# easyEDA.net
KiCad netlist of a schematic drawn in EasyEDA
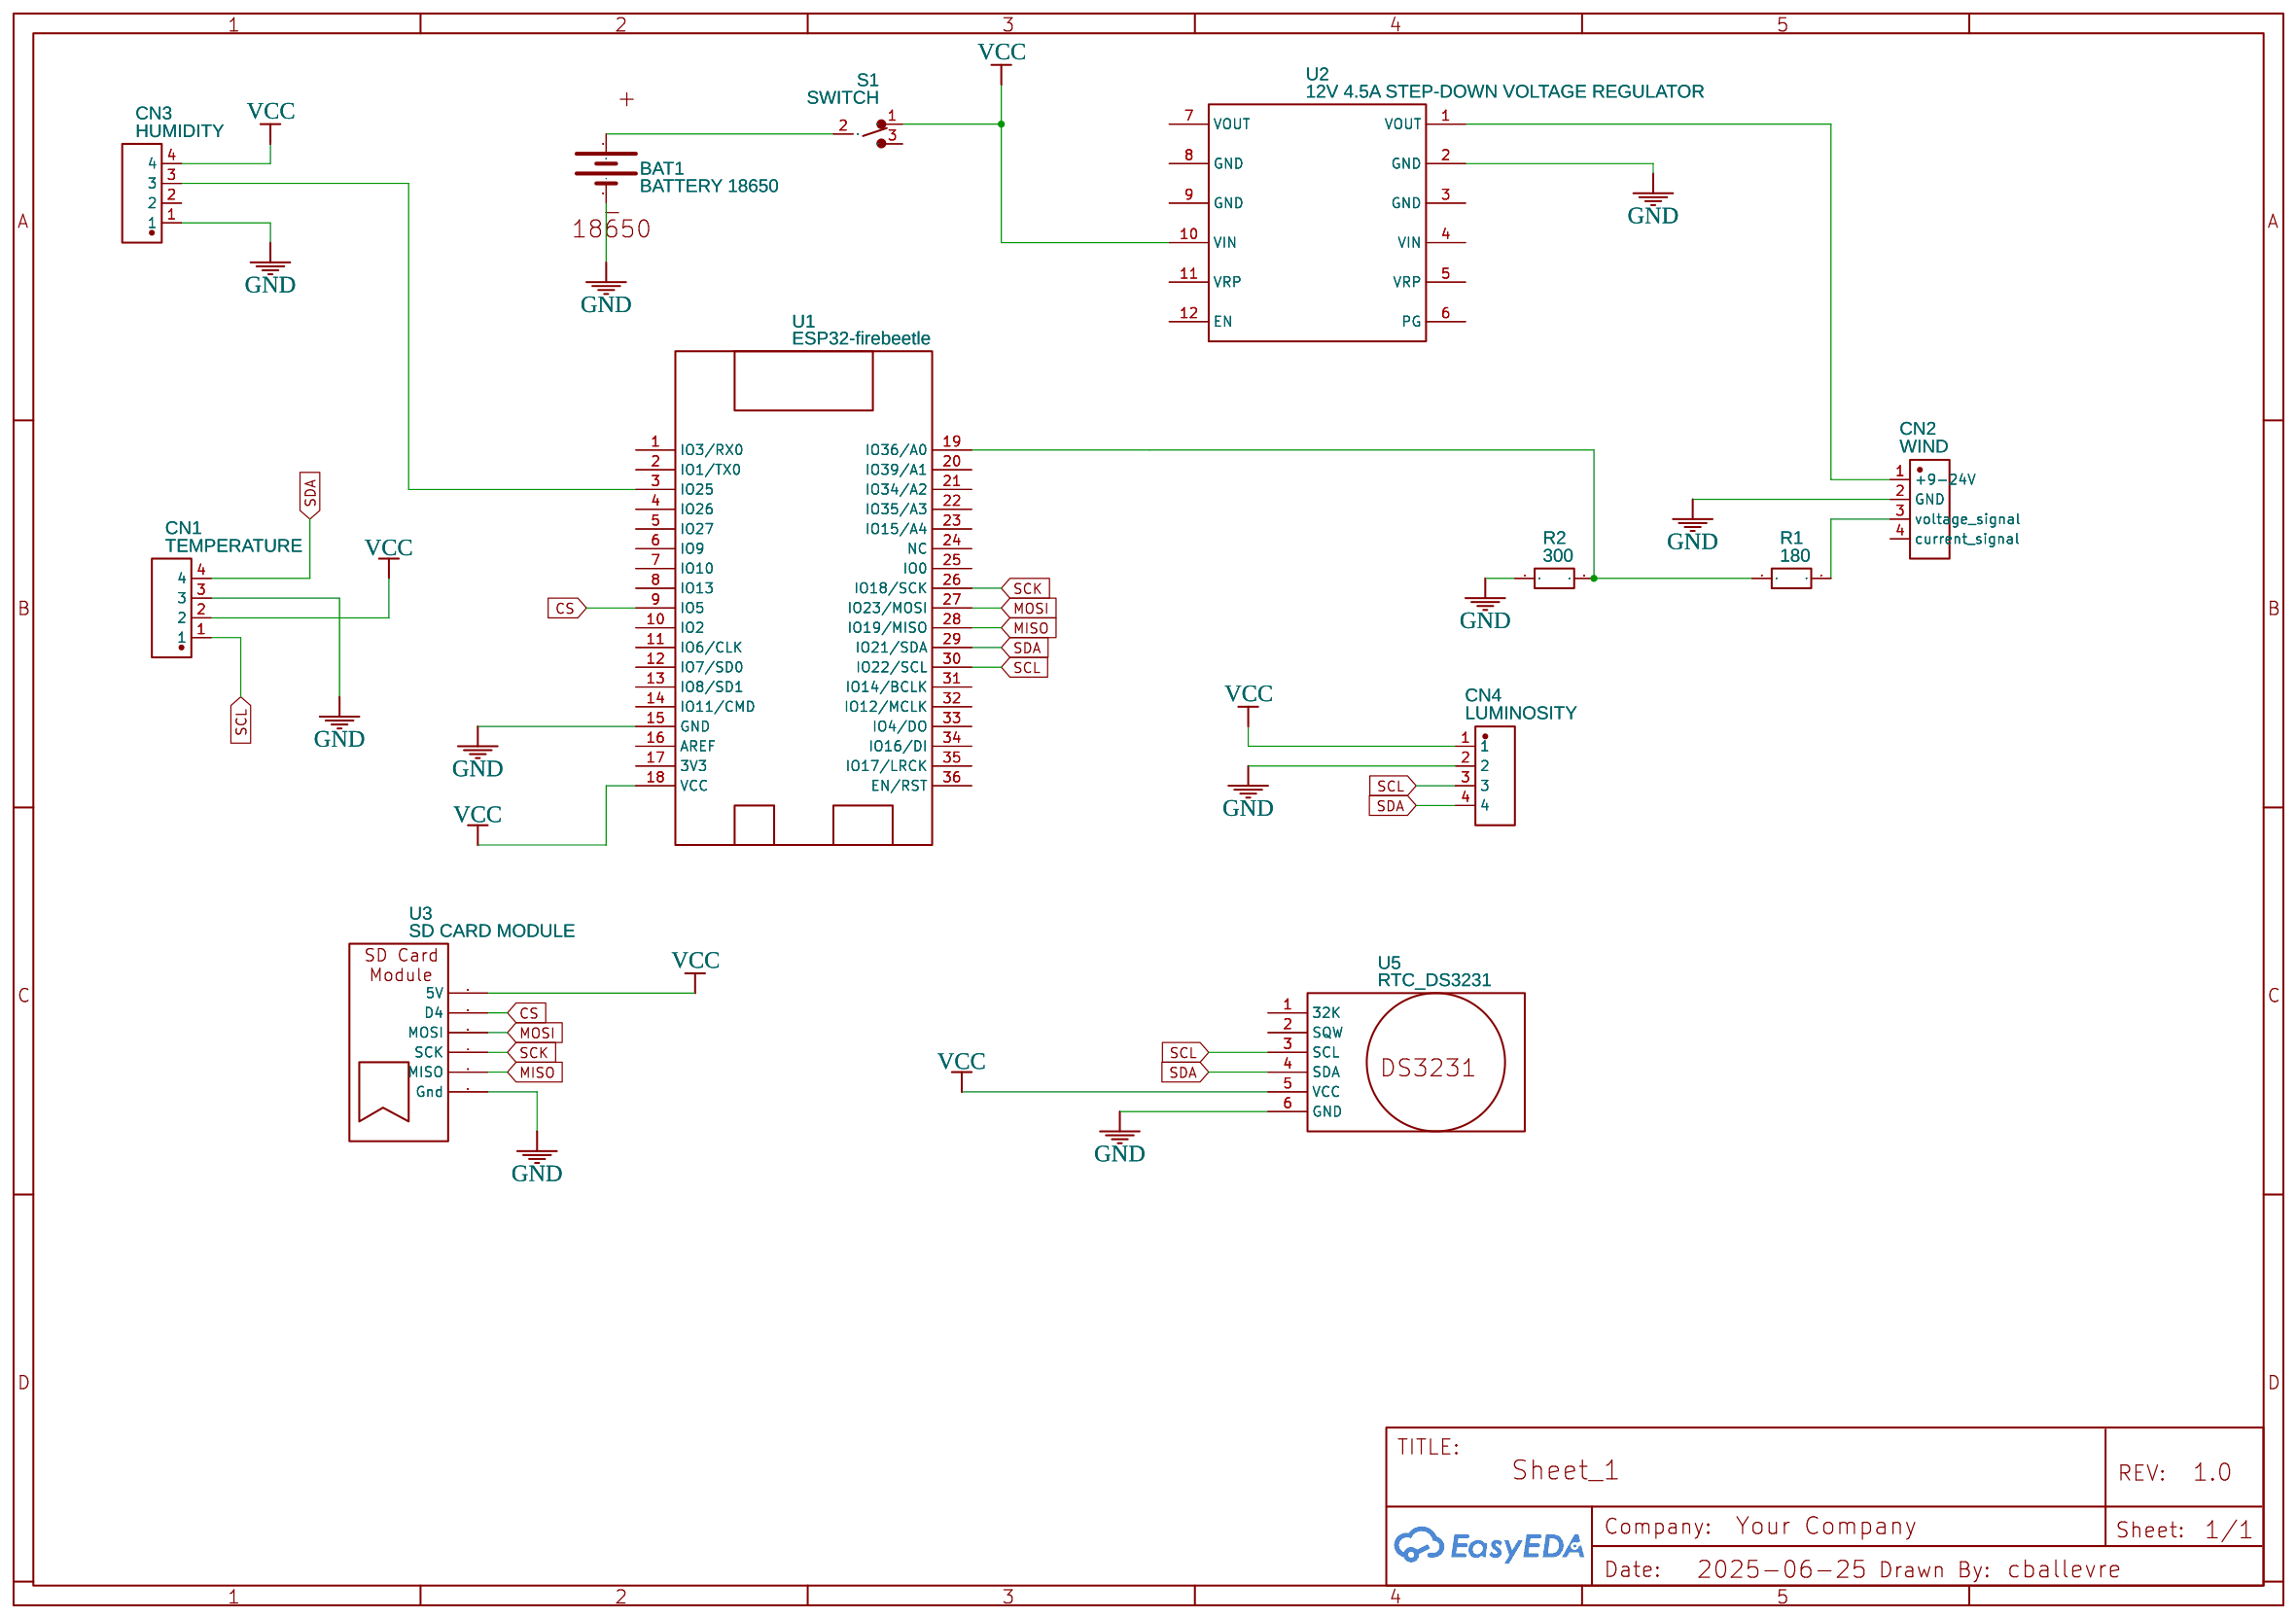
[diagram p0: schematic sheet]

(export (version "E")
  (design (tool "Eeschema 10.0.6"))
  (components
    (comp (ref "BAT1")
      (value "BATTERY 18650")
      (fields (field (name "Manufacturer Part") "battery"))
      (libsource (lib "") (part "BATTERY 18650"))
    )
    (comp (ref "CN1")
      (value "TEMPERATURE")
      (fields (field (name "Manufacturer Part") "Straight 4 pins magnetic connector Female"))
      (libsource (lib "") (part "STRAIGHT 4 PINS MAGNETIC CONNECTOR FEMALE"))
    )
    (comp (ref "CN2")
      (value "WIND")
      (fields (field (name "Manufacturer Part") "Straight 4 pins magnetic connector Female"))
      (libsource (lib "") (part "STRAIGHT 4 PINS MAGNETIC CONNECTOR FEMALE_1"))
    )
    (comp (ref "CN3")
      (value "HUMIDITY")
      (fields (field (name "Manufacturer Part") "Straight 4 pins magnetic connector Female"))
      (libsource (lib "") (part "STRAIGHT 4 PINS MAGNETIC CONNECTOR FEMALE"))
    )
    (comp (ref "CN4")
      (value "LUMINOSITY")
      (fields (field (name "Manufacturer Part") "Straight 4 pins magnetic connector Female"))
      (libsource (lib "") (part "STRAIGHT 4 PINS MAGNETIC CONNECTOR FEMALE_2"))
    )
    (comp (ref "R1") (value "180") (libsource (lib "") (part "R_0603_EU")))
    (comp (ref "R2") (value "300") (libsource (lib "") (part "R_0603_EU")))
    (comp (ref "S1") (value "SWITCH") (libsource (lib "") (part "SWITCH-SLIDE-SPDT-200MA-30V")))
    (comp (ref "U1") (value "ESP32-firebeetle") (libsource (lib "") (part "ESP32-firebeetle")))
    (comp (ref "U2")
      (value "12V 4.5A STEP-DOWN VOLTAGE REGULATOR")
      (libsource (lib "") (part "12V 4.5A STEP-DOWN VOLTAGE REGULATOR"))
    )
    (comp (ref "U3")
      (value "SD CARD MODULE")
      (fields (field (name "Manufacturer Part") "sd card module"))
      (libsource (lib "") (part "SD CARD MODULE COPY JEF"))
    )
    (comp (ref "U5") (value "RTC_DS3231") (libsource (lib "") (part "UhrModul_DS3231")))
  )
  (nets
    (net (code "1") (name "CS") (class "Default")
      (node (ref "U1") (pin "9") (pinfunction "IO5_9") (pintype "unspecified"))
      (node (ref "U3") (pin "5") (pinfunction "D4_5") (pintype "unspecified"))
    )
    (net (code "2") (name "GND") (class "Default")
      (node (ref "BAT1") (pin "2") (pinfunction "-_2") (pintype "passive"))
      (node (ref "CN1") (pin "3") (pinfunction "3_3") (pintype "unspecified"))
      (node (ref "CN2") (pin "2") (pinfunction "GND_2") (pintype "unspecified"))
      (node (ref "CN3") (pin "1") (pinfunction "1_1") (pintype "unspecified"))
      (node (ref "CN4") (pin "2") (pinfunction "2_2") (pintype "unspecified"))
      (node (ref "R2") (pin "1") (pinfunction "1_1") (pintype "unspecified"))
      (node (ref "U1") (pin "15") (pinfunction "GND_15") (pintype "unspecified"))
      (node (ref "U2") (pin "2") (pinfunction "GND_2") (pintype "unspecified"))
      (node (ref "U3") (pin "1") (pinfunction "Gnd_1") (pintype "unspecified"))
      (node (ref "U5") (pin "6") (pinfunction "GND_6") (pintype "unspecified"))
    )
    (net (code "3") (name "MISO") (class "Default")
      (node (ref "U1") (pin "28") (pinfunction "IO19/MISO_28") (pintype "unspecified"))
      (node (ref "U3") (pin "2") (pinfunction "MISO_2") (pintype "unspecified"))
    )
    (net (code "4") (name "MOSI") (class "Default")
      (node (ref "U1") (pin "27") (pinfunction "IO23/MOSI_27") (pintype "unspecified"))
      (node (ref "U3") (pin "3") (pinfunction "MOSI_3") (pintype "unspecified"))
    )
    (net (code "5") (name "Net-(BAT1-+)") (class "Default")
      (node (ref "BAT1") (pin "1") (pinfunction "+_1") (pintype "passive"))
      (node (ref "S1") (pin "2") (pinfunction "2_2") (pintype "input"))
    )
    (net (code "6") (name "Net-(CN2-+9-24V)") (class "Default")
      (node (ref "CN2") (pin "1") (pinfunction "+9-24V_1") (pintype "unspecified"))
      (node (ref "U2") (pin "1") (pinfunction "VOUT_1") (pintype "unspecified"))
    )
    (net (code "7") (name "Net-(CN2-voltage_signal)") (class "Default")
      (node (ref "CN2") (pin "3") (pinfunction "voltage_signal_3") (pintype "unspecified"))
      (node (ref "R1") (pin "2") (pinfunction "2_2") (pintype "unspecified"))
    )
    (net (code "8") (name "Net-(U1-IO25)") (class "Default")
      (node (ref "CN3") (pin "3") (pinfunction "3_3") (pintype "unspecified"))
      (node (ref "U1") (pin "3") (pinfunction "IO25_3") (pintype "unspecified"))
    )
    (net (code "9") (name "Net-(U1-IO36{slash}A0)") (class "Default")
      (node (ref "R1") (pin "1") (pinfunction "1_1") (pintype "unspecified"))
      (node (ref "R2") (pin "2") (pinfunction "2_2") (pintype "unspecified"))
      (node (ref "U1") (pin "19") (pinfunction "IO36/A0_19") (pintype "unspecified"))
    )
    (net (code "10") (name "SCK") (class "Default")
      (node (ref "U1") (pin "26") (pinfunction "IO18/SCK_26") (pintype "unspecified"))
      (node (ref "U3") (pin "4") (pinfunction "SCK_4") (pintype "unspecified"))
    )
    (net (code "11") (name "SCL") (class "Default")
      (node (ref "CN1") (pin "1") (pinfunction "1_1") (pintype "unspecified"))
      (node (ref "CN4") (pin "3") (pinfunction "3_3") (pintype "unspecified"))
      (node (ref "U1") (pin "30") (pinfunction "IO22/SCL_30") (pintype "unspecified"))
      (node (ref "U5") (pin "3") (pinfunction "SCL_3") (pintype "unspecified"))
    )
    (net (code "12") (name "SDA") (class "Default")
      (node (ref "CN1") (pin "4") (pinfunction "4_4") (pintype "unspecified"))
      (node (ref "CN4") (pin "4") (pinfunction "4_4") (pintype "unspecified"))
      (node (ref "U1") (pin "29") (pinfunction "IO21/SDA_29") (pintype "unspecified"))
      (node (ref "U5") (pin "4") (pinfunction "SDA_4") (pintype "unspecified"))
    )
    (net (code "13") (name "VCC") (class "Default")
      (node (ref "CN1") (pin "2") (pinfunction "2_2") (pintype "unspecified"))
      (node (ref "CN3") (pin "4") (pinfunction "4_4") (pintype "unspecified"))
      (node (ref "CN4") (pin "1") (pinfunction "1_1") (pintype "unspecified"))
      (node (ref "S1") (pin "1") (pinfunction "1_1") (pintype "input"))
      (node (ref "U1") (pin "18") (pinfunction "VCC_18") (pintype "unspecified"))
      (node (ref "U2") (pin "10") (pinfunction "VIN_10") (pintype "unspecified"))
      (node (ref "U3") (pin "6") (pinfunction "5V_6") (pintype "unspecified"))
      (node (ref "U5") (pin "5") (pinfunction "VCC_5") (pintype "unspecified"))
    )
    (net (code "14") (name "unconnected-(CN2-current_signal-Pad4)") (class "Default")
      (node (ref "CN2") (pin "4") (pinfunction "current_signal_4") (pintype "unspecified"))
    )
    (net (code "15") (name "unconnected-(CN3-Pad2)") (class "Default")
      (node (ref "CN3") (pin "2") (pinfunction "2_2") (pintype "unspecified"))
    )
    (net (code "16") (name "unconnected-(S1-Pad3)") (class "Default")
      (node (ref "S1") (pin "3") (pinfunction "3_3") (pintype "input"))
    )
    (net (code "17") (name "unconnected-(U1-3V3-Pad17)") (class "Default")
      (node (ref "U1") (pin "17") (pinfunction "3V3_17") (pintype "unspecified"))
    )
    (net (code "18") (name "unconnected-(U1-AREF-Pad16)") (class "Default")
      (node (ref "U1") (pin "16") (pinfunction "AREF_16") (pintype "unspecified"))
    )
    (net (code "19") (name "unconnected-(U1-EN{slash}RST-Pad36)") (class "Default")
      (node (ref "U1") (pin "36") (pinfunction "EN/RST_36") (pintype "unspecified"))
    )
    (net (code "20") (name "unconnected-(U1-IO0-Pad25)") (class "Default")
      (node (ref "U1") (pin "25") (pinfunction "IO0_25") (pintype "unspecified"))
    )
    (net (code "21") (name "unconnected-(U1-IO1{slash}TX0-Pad2)") (class "Default")
      (node (ref "U1") (pin "2") (pinfunction "IO1/TX0_2") (pintype "unspecified"))
    )
    (net (code "22") (name "unconnected-(U1-IO2-Pad10)") (class "Default")
      (node (ref "U1") (pin "10") (pinfunction "IO2_10") (pintype "unspecified"))
    )
    (net (code "23") (name "unconnected-(U1-IO3{slash}RX0-Pad1)") (class "Default")
      (node (ref "U1") (pin "1") (pinfunction "IO3/RX0_1") (pintype "unspecified"))
    )
    (net (code "24") (name "unconnected-(U1-IO4{slash}DO-Pad33)") (class "Default")
      (node (ref "U1") (pin "33") (pinfunction "IO4/DO_33") (pintype "unspecified"))
    )
    (net (code "25") (name "unconnected-(U1-IO6{slash}CLK-Pad11)") (class "Default")
      (node (ref "U1") (pin "11") (pinfunction "IO6/CLK_11") (pintype "unspecified"))
    )
    (net (code "26") (name "unconnected-(U1-IO7{slash}SD0-Pad12)") (class "Default")
      (node (ref "U1") (pin "12") (pinfunction "IO7/SD0_12") (pintype "unspecified"))
    )
    (net (code "27") (name "unconnected-(U1-IO8{slash}SD1-Pad13)") (class "Default")
      (node (ref "U1") (pin "13") (pinfunction "IO8/SD1_13") (pintype "unspecified"))
    )
    (net (code "28") (name "unconnected-(U1-IO9-Pad6)") (class "Default")
      (node (ref "U1") (pin "6") (pinfunction "IO9_6") (pintype "unspecified"))
    )
    (net (code "29") (name "unconnected-(U1-IO10-Pad7)") (class "Default")
      (node (ref "U1") (pin "7") (pinfunction "IO10_7") (pintype "unspecified"))
    )
    (net (code "30") (name "unconnected-(U1-IO11{slash}CMD-Pad14)") (class "Default")
      (node (ref "U1") (pin "14") (pinfunction "IO11/CMD_14") (pintype "unspecified"))
    )
    (net (code "31") (name "unconnected-(U1-IO12{slash}MCLK-Pad32)") (class "Default")
      (node (ref "U1") (pin "32") (pinfunction "IO12/MCLK_32") (pintype "unspecified"))
    )
    (net (code "32") (name "unconnected-(U1-IO13-Pad8)") (class "Default")
      (node (ref "U1") (pin "8") (pinfunction "IO13_8") (pintype "unspecified"))
    )
    (net (code "33") (name "unconnected-(U1-IO14{slash}BCLK-Pad31)") (class "Default")
      (node (ref "U1") (pin "31") (pinfunction "IO14/BCLK_31") (pintype "unspecified"))
    )
    (net (code "34") (name "unconnected-(U1-IO15{slash}A4-Pad23)") (class "Default")
      (node (ref "U1") (pin "23") (pinfunction "IO15/A4_23") (pintype "unspecified"))
    )
    (net (code "35") (name "unconnected-(U1-IO16{slash}DI-Pad34)") (class "Default")
      (node (ref "U1") (pin "34") (pinfunction "IO16/DI_34") (pintype "unspecified"))
    )
    (net (code "36") (name "unconnected-(U1-IO17{slash}LRCK-Pad35)") (class "Default")
      (node (ref "U1") (pin "35") (pinfunction "IO17/LRCK_35") (pintype "unspecified"))
    )
    (net (code "37") (name "unconnected-(U1-IO26-Pad4)") (class "Default")
      (node (ref "U1") (pin "4") (pinfunction "IO26_4") (pintype "unspecified"))
    )
    (net (code "38") (name "unconnected-(U1-IO27-Pad5)") (class "Default")
      (node (ref "U1") (pin "5") (pinfunction "IO27_5") (pintype "unspecified"))
    )
    (net (code "39") (name "unconnected-(U1-IO34{slash}A2-Pad21)") (class "Default")
      (node (ref "U1") (pin "21") (pinfunction "IO34/A2_21") (pintype "unspecified"))
    )
    (net (code "40") (name "unconnected-(U1-IO35{slash}A3-Pad22)") (class "Default")
      (node (ref "U1") (pin "22") (pinfunction "IO35/A3_22") (pintype "unspecified"))
    )
    (net (code "41") (name "unconnected-(U1-IO39{slash}A1-Pad20)") (class "Default")
      (node (ref "U1") (pin "20") (pinfunction "IO39/A1_20") (pintype "unspecified"))
    )
    (net (code "42") (name "unconnected-(U1-NC-Pad24)") (class "Default")
      (node (ref "U1") (pin "24") (pinfunction "NC_24") (pintype "unspecified"))
    )
    (net (code "43") (name "unconnected-(U2-EN-Pad12)") (class "Default")
      (node (ref "U2") (pin "12") (pinfunction "EN_12") (pintype "unspecified"))
    )
    (net (code "44") (name "unconnected-(U2-GND-Pad3)") (class "Default")
      (node (ref "U2") (pin "3") (pinfunction "GND_3") (pintype "unspecified"))
    )
    (net (code "45") (name "unconnected-(U2-GND-Pad8)") (class "Default")
      (node (ref "U2") (pin "8") (pinfunction "GND_8") (pintype "unspecified"))
    )
    (net (code "46") (name "unconnected-(U2-GND-Pad9)") (class "Default")
      (node (ref "U2") (pin "9") (pinfunction "GND_9") (pintype "unspecified"))
    )
    (net (code "47") (name "unconnected-(U2-PG-Pad6)") (class "Default")
      (node (ref "U2") (pin "6") (pinfunction "PG_6") (pintype "unspecified"))
    )
    (net (code "48") (name "unconnected-(U2-VIN-Pad4)") (class "Default")
      (node (ref "U2") (pin "4") (pinfunction "VIN_4") (pintype "unspecified"))
    )
    (net (code "49") (name "unconnected-(U2-VOUT-Pad7)") (class "Default")
      (node (ref "U2") (pin "7") (pinfunction "VOUT_7") (pintype "unspecified"))
    )
    (net (code "50") (name "unconnected-(U2-VRP-Pad5)") (class "Default")
      (node (ref "U2") (pin "5") (pinfunction "VRP_5") (pintype "unspecified"))
    )
    (net (code "51") (name "unconnected-(U2-VRP-Pad11)") (class "Default")
      (node (ref "U2") (pin "11") (pinfunction "VRP_11") (pintype "unspecified"))
    )
    (net (code "52") (name "unconnected-(U5-32K-Pad1)") (class "Default")
      (node (ref "U5") (pin "1") (pinfunction "32K_1") (pintype "unspecified"))
    )
    (net (code "53") (name "unconnected-(U5-SQW-Pad2)") (class "Default")
      (node (ref "U5") (pin "2") (pinfunction "SQW_2") (pintype "unspecified"))
    )
  )
)
